# Power_ATX.net
KiCad netlist of a schematic drawn in Altium Designer
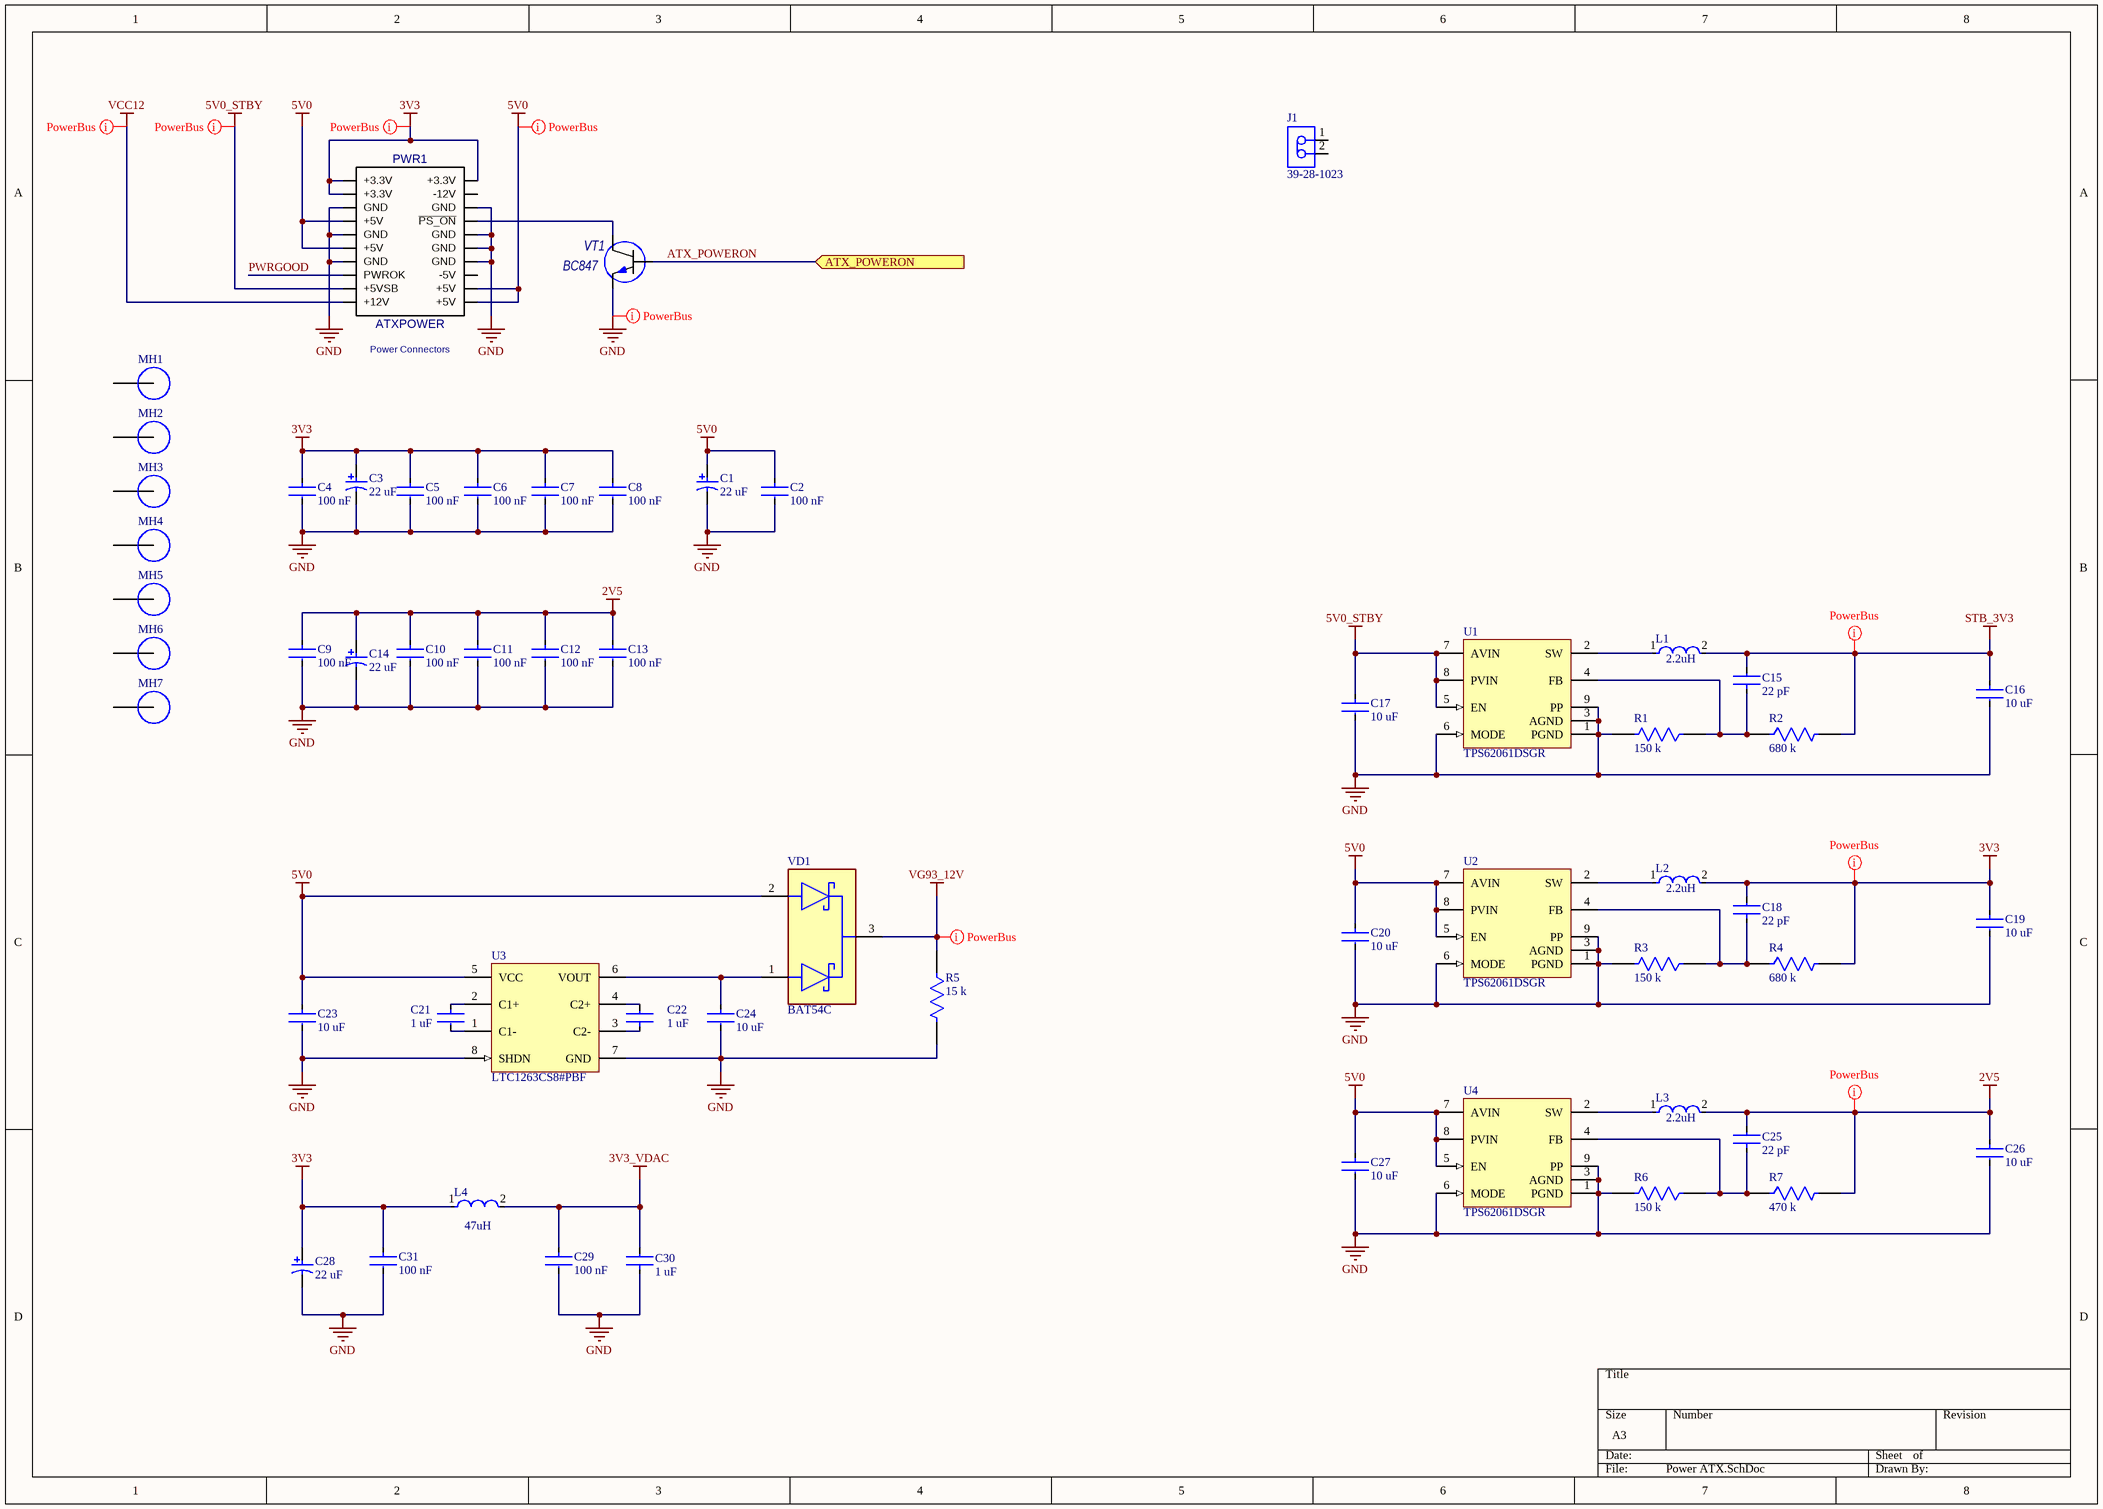
[diagram p0: Power ATX.SchDoc]

(export (version "E")
  (design (tool "Eeschema 10.0.6"))
  (components
    (comp (ref "C1")
      (value "EC1210-22uF")
      (footprint "AVX-TAJ-B-2_M")
      (description "Standard Tantalum, 22 uF, +/- 10%, 16 V, -55 to 125 degC, 2-Pin SMD (1210), RoHS, Tape and Reel")
      (fields
        (field (name "CAPACITANCE") "22 uF")
        (field (name "MANUFACTURER") "Kyocera AVX")
        (field (name "MANUFACTURER PART NUMBER") "TAJB226K016RNJ")
      )
      (libsource (lib "zxevo") (part "EC1210-22uF"))
    )
    (comp (ref "C2")
      (value "CC0805-1.5pF")
      (footprint "CC0805")
      (description "CL21 Series 0805 1.5pF 50V ±0.25pF Tolerance C0G Multilayer Ceramic Chip Capacitor")
      (fields
        (field (name "MANUFACTURER PART NUMBER") "CL21C1R5CBANNNC")
        (field (name "CAPACITANCE") "100 nF")
        (field (name "MANUFACTURER") "Samsung")
      )
      (libsource (lib "zxevo") (part "CC0805"))
    )
    (comp (ref "C3")
      (value "EC1210-22uF")
      (footprint "AVX-TAJ-B-2_M")
      (description "Standard Tantalum, 22 uF, +/- 10%, 16 V, -55 to 125 degC, 2-Pin SMD (1210), RoHS, Tape and Reel")
      (fields
        (field (name "CAPACITANCE") "22 uF")
        (field (name "MANUFACTURER") "Kyocera AVX")
        (field (name "MANUFACTURER PART NUMBER") "TAJB226K016RNJ")
      )
      (libsource (lib "zxevo") (part "EC1210-22uF"))
    )
    (comp (ref "C4")
      (value "CC0805-1.5pF")
      (footprint "CC0805")
      (description "CL21 Series 0805 1.5pF 50V ±0.25pF Tolerance C0G Multilayer Ceramic Chip Capacitor")
      (fields
        (field (name "MANUFACTURER PART NUMBER") "CL21C1R5CBANNNC")
        (field (name "CAPACITANCE") "100 nF")
        (field (name "MANUFACTURER") "Samsung")
      )
      (libsource (lib "zxevo") (part "CC0805"))
    )
    (comp (ref "C5")
      (value "CC0805-1.5pF")
      (footprint "CC0805")
      (description "CL21 Series 0805 1.5pF 50V ±0.25pF Tolerance C0G Multilayer Ceramic Chip Capacitor")
      (fields
        (field (name "MANUFACTURER PART NUMBER") "CL21C1R5CBANNNC")
        (field (name "CAPACITANCE") "100 nF")
        (field (name "MANUFACTURER") "Samsung")
      )
      (libsource (lib "zxevo") (part "CC0805"))
    )
    (comp (ref "C6")
      (value "CC0805-1.5pF")
      (footprint "CC0805")
      (description "CL21 Series 0805 1.5pF 50V ±0.25pF Tolerance C0G Multilayer Ceramic Chip Capacitor")
      (fields
        (field (name "MANUFACTURER PART NUMBER") "CL21C1R5CBANNNC")
        (field (name "CAPACITANCE") "100 nF")
        (field (name "MANUFACTURER") "Samsung")
      )
      (libsource (lib "zxevo") (part "CC0805"))
    )
    (comp (ref "C7")
      (value "CC0805-1.5pF")
      (footprint "CC0805")
      (description "CL21 Series 0805 1.5pF 50V ±0.25pF Tolerance C0G Multilayer Ceramic Chip Capacitor")
      (fields
        (field (name "MANUFACTURER PART NUMBER") "CL21C1R5CBANNNC")
        (field (name "CAPACITANCE") "100 nF")
        (field (name "MANUFACTURER") "Samsung")
      )
      (libsource (lib "zxevo") (part "CC0805"))
    )
    (comp (ref "C8")
      (value "CC0805-1.5pF")
      (footprint "CC0805")
      (description "CL21 Series 0805 1.5pF 50V ±0.25pF Tolerance C0G Multilayer Ceramic Chip Capacitor")
      (fields
        (field (name "MANUFACTURER PART NUMBER") "CL21C1R5CBANNNC")
        (field (name "CAPACITANCE") "100 nF")
        (field (name "MANUFACTURER") "Samsung")
      )
      (libsource (lib "zxevo") (part "CC0805"))
    )
    (comp (ref "C9")
      (value "CC0805-1.5pF")
      (footprint "CC0805")
      (description "CL21 Series 0805 1.5pF 50V ±0.25pF Tolerance C0G Multilayer Ceramic Chip Capacitor")
      (fields
        (field (name "MANUFACTURER PART NUMBER") "CL21C1R5CBANNNC")
        (field (name "CAPACITANCE") "100 nF")
        (field (name "MANUFACTURER") "Samsung")
      )
      (libsource (lib "zxevo") (part "CC0805"))
    )
    (comp (ref "C10")
      (value "CC0805-1.5pF")
      (footprint "CC0805")
      (description "CL21 Series 0805 1.5pF 50V ±0.25pF Tolerance C0G Multilayer Ceramic Chip Capacitor")
      (fields
        (field (name "MANUFACTURER PART NUMBER") "CL21C1R5CBANNNC")
        (field (name "CAPACITANCE") "100 nF")
        (field (name "MANUFACTURER") "Samsung")
      )
      (libsource (lib "zxevo") (part "CC0805"))
    )
    (comp (ref "C11")
      (value "CC0805-1.5pF")
      (footprint "CC0805")
      (description "CL21 Series 0805 1.5pF 50V ±0.25pF Tolerance C0G Multilayer Ceramic Chip Capacitor")
      (fields
        (field (name "MANUFACTURER PART NUMBER") "CL21C1R5CBANNNC")
        (field (name "CAPACITANCE") "100 nF")
        (field (name "MANUFACTURER") "Samsung")
      )
      (libsource (lib "zxevo") (part "CC0805"))
    )
    (comp (ref "C12")
      (value "CC0805-1.5pF")
      (footprint "CC0805")
      (description "CL21 Series 0805 1.5pF 50V ±0.25pF Tolerance C0G Multilayer Ceramic Chip Capacitor")
      (fields
        (field (name "MANUFACTURER PART NUMBER") "CL21C1R5CBANNNC")
        (field (name "CAPACITANCE") "100 nF")
        (field (name "MANUFACTURER") "Samsung")
      )
      (libsource (lib "zxevo") (part "CC0805"))
    )
    (comp (ref "C13")
      (value "CC0805-1.5pF")
      (footprint "CC0805")
      (description "CL21 Series 0805 1.5pF 50V ±0.25pF Tolerance C0G Multilayer Ceramic Chip Capacitor")
      (fields
        (field (name "MANUFACTURER PART NUMBER") "CL21C1R5CBANNNC")
        (field (name "CAPACITANCE") "100 nF")
        (field (name "MANUFACTURER") "Samsung")
      )
      (libsource (lib "zxevo") (part "CC0805"))
    )
    (comp (ref "C14")
      (value "EC1210-22uF")
      (footprint "AVX-TAJ-B-2_M")
      (description "Standard Tantalum, 22 uF, +/- 10%, 16 V, -55 to 125 degC, 2-Pin SMD (1210), RoHS, Tape and Reel")
      (fields
        (field (name "CAPACITANCE") "22 uF")
        (field (name "MANUFACTURER") "Kyocera AVX")
        (field (name "MANUFACTURER PART NUMBER") "TAJB226K016RNJ")
      )
      (libsource (lib "zxevo") (part "EC1210-22uF"))
    )
    (comp (ref "C15")
      (value "CC0805-1.5pF")
      (footprint "CC0805")
      (description "CL21 Series 0805 1.5pF 50V ±0.25pF Tolerance C0G Multilayer Ceramic Chip Capacitor")
      (fields
        (field (name "MANUFACTURER PART NUMBER") "CL21C1R5CBANNNC")
        (field (name "MANUFACTURER") "Samsung")
        (field (name "CAPACITANCE") "22 pF")
      )
      (libsource (lib "zxevo") (part "CC0805"))
    )
    (comp (ref "C16")
      (value "CC0805-1.5pF")
      (footprint "CC0805")
      (description "CL21 Series 0805 1.5pF 50V ±0.25pF Tolerance C0G Multilayer Ceramic Chip Capacitor")
      (fields
        (field (name "MANUFACTURER PART NUMBER") "CL21C1R5CBANNNC")
        (field (name "MANUFACTURER") "Samsung")
        (field (name "CAPACITANCE") "10 uF")
      )
      (libsource (lib "zxevo") (part "CC0805"))
    )
    (comp (ref "C17")
      (value "CC0805-1.5pF")
      (footprint "CC0805")
      (description "CL21 Series 0805 1.5pF 50V ±0.25pF Tolerance C0G Multilayer Ceramic Chip Capacitor")
      (fields
        (field (name "MANUFACTURER PART NUMBER") "CL21C1R5CBANNNC")
        (field (name "MANUFACTURER") "Samsung")
        (field (name "CAPACITANCE") "10 uF")
      )
      (libsource (lib "zxevo") (part "CC0805"))
    )
    (comp (ref "C18")
      (value "CC0805-1.5pF")
      (footprint "CC0805")
      (description "CL21 Series 0805 1.5pF 50V ±0.25pF Tolerance C0G Multilayer Ceramic Chip Capacitor")
      (fields
        (field (name "MANUFACTURER PART NUMBER") "CL21C1R5CBANNNC")
        (field (name "MANUFACTURER") "Samsung")
        (field (name "CAPACITANCE") "22 pF")
      )
      (libsource (lib "zxevo") (part "CC0805"))
    )
    (comp (ref "C19")
      (value "CC0805-1.5pF")
      (footprint "CC0805")
      (description "CL21 Series 0805 1.5pF 50V ±0.25pF Tolerance C0G Multilayer Ceramic Chip Capacitor")
      (fields
        (field (name "MANUFACTURER PART NUMBER") "CL21C1R5CBANNNC")
        (field (name "MANUFACTURER") "Samsung")
        (field (name "CAPACITANCE") "10 uF")
      )
      (libsource (lib "zxevo") (part "CC0805"))
    )
    (comp (ref "C20")
      (value "CC0805-1.5pF")
      (footprint "CC0805")
      (description "CL21 Series 0805 1.5pF 50V ±0.25pF Tolerance C0G Multilayer Ceramic Chip Capacitor")
      (fields
        (field (name "MANUFACTURER PART NUMBER") "CL21C1R5CBANNNC")
        (field (name "MANUFACTURER") "Samsung")
        (field (name "CAPACITANCE") "10 uF")
      )
      (libsource (lib "zxevo") (part "CC0805"))
    )
    (comp (ref "C21")
      (value "CC0805-1.5pF")
      (footprint "CC0805")
      (description "CL21 Series 0805 1.5pF 50V ±0.25pF Tolerance C0G Multilayer Ceramic Chip Capacitor")
      (fields
        (field (name "CAPACITANCE") "1 uF")
        (field (name "MANUFACTURER") "Samsung")
        (field (name "MANUFACTURER PART NUMBER") "CL21C1R5CBANNNC")
      )
      (libsource (lib "zxevo") (part "CC0805"))
    )
    (comp (ref "C22")
      (value "CC0805-1.5pF")
      (footprint "CC0805")
      (description "CL21 Series 0805 1.5pF 50V ±0.25pF Tolerance C0G Multilayer Ceramic Chip Capacitor")
      (fields
        (field (name "CAPACITANCE") "1 uF")
        (field (name "MANUFACTURER") "Samsung")
        (field (name "MANUFACTURER PART NUMBER") "CL21C1R5CBANNNC")
      )
      (libsource (lib "zxevo") (part "CC0805"))
    )
    (comp (ref "C23")
      (value "CC0805-1.5pF")
      (footprint "CC0805")
      (description "CL21 Series 0805 1.5pF 50V ±0.25pF Tolerance C0G Multilayer Ceramic Chip Capacitor")
      (fields
        (field (name "MANUFACTURER PART NUMBER") "CL21C1R5CBANNNC")
        (field (name "MANUFACTURER") "Samsung")
        (field (name "CAPACITANCE") "10 uF")
      )
      (libsource (lib "zxevo") (part "CC0805"))
    )
    (comp (ref "C24")
      (value "CC0805-1.5pF")
      (footprint "CC0805")
      (description "CL21 Series 0805 1.5pF 50V ±0.25pF Tolerance C0G Multilayer Ceramic Chip Capacitor")
      (fields
        (field (name "MANUFACTURER PART NUMBER") "CL21C1R5CBANNNC")
        (field (name "MANUFACTURER") "Samsung")
        (field (name "CAPACITANCE") "10 uF")
      )
      (libsource (lib "zxevo") (part "CC0805"))
    )
    (comp (ref "C25")
      (value "CC0805-1.5pF")
      (footprint "CC0805")
      (description "CL21 Series 0805 1.5pF 50V ±0.25pF Tolerance C0G Multilayer Ceramic Chip Capacitor")
      (fields
        (field (name "MANUFACTURER PART NUMBER") "CL21C1R5CBANNNC")
        (field (name "MANUFACTURER") "Samsung")
        (field (name "CAPACITANCE") "22 pF")
      )
      (libsource (lib "zxevo") (part "CC0805"))
    )
    (comp (ref "C26")
      (value "CC0805-1.5pF")
      (footprint "CC0805")
      (description "CL21 Series 0805 1.5pF 50V ±0.25pF Tolerance C0G Multilayer Ceramic Chip Capacitor")
      (fields
        (field (name "MANUFACTURER PART NUMBER") "CL21C1R5CBANNNC")
        (field (name "MANUFACTURER") "Samsung")
        (field (name "CAPACITANCE") "10 uF")
      )
      (libsource (lib "zxevo") (part "CC0805"))
    )
    (comp (ref "C27")
      (value "CC0805-1.5pF")
      (footprint "CC0805")
      (description "CL21 Series 0805 1.5pF 50V ±0.25pF Tolerance C0G Multilayer Ceramic Chip Capacitor")
      (fields
        (field (name "MANUFACTURER PART NUMBER") "CL21C1R5CBANNNC")
        (field (name "MANUFACTURER") "Samsung")
        (field (name "CAPACITANCE") "10 uF")
      )
      (libsource (lib "zxevo") (part "CC0805"))
    )
    (comp (ref "C28")
      (value "EC1210-22uF")
      (footprint "AVX-TAJ-B-2_M")
      (description "Standard Tantalum, 22 uF, +/- 10%, 16 V, -55 to 125 degC, 2-Pin SMD (1210), RoHS, Tape and Reel")
      (fields
        (field (name "CAPACITANCE") "22 uF")
        (field (name "MANUFACTURER") "Kyocera AVX")
        (field (name "MANUFACTURER PART NUMBER") "TAJB226K016RNJ")
      )
      (libsource (lib "zxevo") (part "EC1210-22uF"))
    )
    (comp (ref "C29")
      (value "CC0805-1.5pF")
      (footprint "CC0805")
      (description "CL21 Series 0805 1.5pF 50V ±0.25pF Tolerance C0G Multilayer Ceramic Chip Capacitor")
      (fields
        (field (name "MANUFACTURER PART NUMBER") "CL21C1R5CBANNNC")
        (field (name "CAPACITANCE") "100 nF")
        (field (name "MANUFACTURER") "Samsung")
      )
      (libsource (lib "zxevo") (part "CC0805"))
    )
    (comp (ref "C30")
      (value "CC0805-1.5pF")
      (footprint "CC0805")
      (description "CL21 Series 0805 1.5pF 50V ±0.25pF Tolerance C0G Multilayer Ceramic Chip Capacitor")
      (fields
        (field (name "CAPACITANCE") "1 uF")
        (field (name "MANUFACTURER") "Samsung")
        (field (name "MANUFACTURER PART NUMBER") "CL21C1R5CBANNNC")
      )
      (libsource (lib "zxevo") (part "CC0805"))
    )
    (comp (ref "C31")
      (value "CC0805-1.5pF")
      (footprint "CC0805")
      (description "CL21 Series 0805 1.5pF 50V ±0.25pF Tolerance C0G Multilayer Ceramic Chip Capacitor")
      (fields
        (field (name "MANUFACTURER PART NUMBER") "CL21C1R5CBANNNC")
        (field (name "CAPACITANCE") "100 nF")
        (field (name "MANUFACTURER") "Samsung")
      )
      (libsource (lib "zxevo") (part "CC0805"))
    )
    (comp (ref "J1")
      (value "39-28-1023")
      (footprint "MOLX-39-28-1023-2_V")
      (fields (field (name "MANUFACTURER") "Molex"))
      (libsource (lib "Altium Content Vault") (part "CN-2P-F-QF2"))
    )
    (comp (ref "L1")
      (value "NR6028T2R2N")
      (footprint "FP-NR6028-MFG")
      (description "SMD Power Inductors 2.2uH ±30% 3.7A 26mΩ")
      (fields (field (name "TOLERANCE") "30%") (field (name "INDUCTANCE") "2.2uH"))
      (libsource (lib "Altium Content Vault") (part "725321dda6339637d4d059423bc1c3c"))
    )
    (comp (ref "L2")
      (value "NR6028T2R2N")
      (footprint "FP-NR6028-MFG")
      (description "SMD Power Inductors 2.2uH ±30% 3.7A 26mΩ")
      (fields (field (name "TOLERANCE") "30%") (field (name "INDUCTANCE") "2.2uH"))
      (libsource (lib "Altium Content Vault") (part "725321dda6339637d4d059423bc1c3c"))
    )
    (comp (ref "L3")
      (value "NR6028T2R2N")
      (footprint "FP-NR6028-MFG")
      (description "SMD Power Inductors 2.2uH ±30% 3.7A 26mΩ")
      (fields (field (name "TOLERANCE") "30%") (field (name "INDUCTANCE") "2.2uH"))
      (libsource (lib "Altium Content Vault") (part "725321dda6339637d4d059423bc1c3c"))
    )
    (comp (ref "L4")
      (value "NR6028T470M")
      (footprint "FP-NR6028-MFG")
      (description "SMD Power Inductors 47uH ±20% 0.92A 0.39Ω")
      (fields (field (name "INDUCTANCE") "47uH") (field (name "TOLERANCE") "20%"))
      (libsource (lib "Altium Content Vault") (part "725321dda6339637d4d059423bc1c3c"))
    )
    (comp (ref "MH1")
      (value "MOUNT HOLE")
      (footprint "MOUNT HOLE")
      (libsource (lib "zxevo") (part "MOUNT HOLE"))
    )
    (comp (ref "MH2")
      (value "MOUNT HOLE")
      (footprint "MOUNT HOLE")
      (libsource (lib "zxevo") (part "MOUNT HOLE"))
    )
    (comp (ref "MH3")
      (value "MOUNT HOLE")
      (footprint "MOUNT HOLE")
      (libsource (lib "zxevo") (part "MOUNT HOLE"))
    )
    (comp (ref "MH4")
      (value "MOUNT HOLE")
      (footprint "MOUNT HOLE")
      (libsource (lib "zxevo") (part "MOUNT HOLE"))
    )
    (comp (ref "MH5")
      (value "MOUNT HOLE")
      (footprint "MOUNT HOLE")
      (libsource (lib "zxevo") (part "MOUNT HOLE"))
    )
    (comp (ref "MH6")
      (value "MOUNT HOLE")
      (footprint "MOUNT HOLE")
      (libsource (lib "zxevo") (part "MOUNT HOLE"))
    )
    (comp (ref "MH7")
      (value "MOUNT HOLE")
      (footprint "MOUNT HOLE")
      (libsource (lib "zxevo") (part "MOUNT HOLE"))
    )
    (comp (ref "PWR1") (value "ATXPOWER") (footprint "ATXPOWER") (libsource (lib "zxevo") (part "ATXPOWER")))
    (comp (ref "R1")
      (value "CR0805-51")
      (footprint "CR0805")
      (description "51Ω ±0.5% 0.1W 1/10W Chip Resistor 0805 (2012 Metric) Thin Film")
      (fields
        (field (name "MANUFACTURER PART NUMBER") "RR1220Q-510-D")
        (field (name "MANUFACTURER") "Susumu")
        (field (name "RESISTANCE") "150 k")
      )
      (libsource (lib "zxevo") (part "CR0805"))
    )
    (comp (ref "R2")
      (value "CR0805-51")
      (footprint "CR0805")
      (description "51Ω ±0.5% 0.1W 1/10W Chip Resistor 0805 (2012 Metric) Thin Film")
      (fields
        (field (name "MANUFACTURER PART NUMBER") "RR1220Q-510-D")
        (field (name "MANUFACTURER") "Susumu")
        (field (name "RESISTANCE") "680 k")
      )
      (libsource (lib "zxevo") (part "CR0805"))
    )
    (comp (ref "R3")
      (value "CR0805-51")
      (footprint "CR0805")
      (description "51Ω ±0.5% 0.1W 1/10W Chip Resistor 0805 (2012 Metric) Thin Film")
      (fields
        (field (name "MANUFACTURER PART NUMBER") "RR1220Q-510-D")
        (field (name "MANUFACTURER") "Susumu")
        (field (name "RESISTANCE") "150 k")
      )
      (libsource (lib "zxevo") (part "CR0805"))
    )
    (comp (ref "R4")
      (value "CR0805-51")
      (footprint "CR0805")
      (description "51Ω ±0.5% 0.1W 1/10W Chip Resistor 0805 (2012 Metric) Thin Film")
      (fields
        (field (name "MANUFACTURER PART NUMBER") "RR1220Q-510-D")
        (field (name "MANUFACTURER") "Susumu")
        (field (name "RESISTANCE") "680 k")
      )
      (libsource (lib "zxevo") (part "CR0805"))
    )
    (comp (ref "R5")
      (value "CR0805-51")
      (footprint "CR0805")
      (description "51Ω ±0.5% 0.1W 1/10W Chip Resistor 0805 (2012 Metric) Thin Film")
      (fields
        (field (name "MANUFACTURER PART NUMBER") "RR1220Q-510-D")
        (field (name "MANUFACTURER") "Susumu")
        (field (name "RESISTANCE") "15 k")
      )
      (libsource (lib "zxevo") (part "CR0805"))
    )
    (comp (ref "R6")
      (value "CR0805-51")
      (footprint "CR0805")
      (description "51Ω ±0.5% 0.1W 1/10W Chip Resistor 0805 (2012 Metric) Thin Film")
      (fields
        (field (name "MANUFACTURER PART NUMBER") "RR1220Q-510-D")
        (field (name "MANUFACTURER") "Susumu")
        (field (name "RESISTANCE") "150 k")
      )
      (libsource (lib "zxevo") (part "CR0805"))
    )
    (comp (ref "R7")
      (value "CR0805-51")
      (footprint "CR0805")
      (description "51Ω ±0.5% 0.1W 1/10W Chip Resistor 0805 (2012 Metric) Thin Film")
      (fields
        (field (name "MANUFACTURER PART NUMBER") "RR1220Q-510-D")
        (field (name "MANUFACTURER") "Susumu")
        (field (name "RESISTANCE") "470 k")
      )
      (libsource (lib "zxevo") (part "CR0805"))
    )
    (comp (ref "U1")
      (value "TPS62061DSGR")
      (footprint "DSG0008A_V")
      (fields (field (name "MANUFACTURER") "Texas Instruments"))
      (libsource (lib "Altium Content Vault") (part "TI-TPS62061DSG8-1600X900TP"))
    )
    (comp (ref "U2")
      (value "TPS62061DSGR")
      (footprint "DSG0008A_V")
      (fields (field (name "MANUFACTURER") "Texas Instruments"))
      (libsource (lib "Altium Content Vault") (part "TI-TPS62061DSG8-1600X900TP"))
    )
    (comp (ref "U3")
      (value "LTC1263CS8#PBF")
      (footprint "LT-S8-8_N")
      (fields (field (name "MANUFACTURER") "Linear Technology"))
      (libsource (lib "Altium Content Vault") (part "LT-LTC1262_1263-8"))
    )
    (comp (ref "U4")
      (value "TPS62061DSGR")
      (footprint "DSG0008A_V")
      (fields (field (name "MANUFACTURER") "Texas Instruments"))
      (libsource (lib "Altium Content Vault") (part "TI-TPS62061DSG8-1600X900TP"))
    )
    (comp (ref "VD1")
      (value "BAT54C")
      (footprint "SOT-23")
      (description "DIODE ARRAY SCHOTTKY 30V SOT23-3")
      (fields (field (name "MANUFACTURER") "ON Semiconductor / Fairchild"))
      (libsource (lib "zxevo") (part "BAT54C"))
    )
    (comp (ref "VT1") (value "BC847") (footprint "SOT-23") (libsource (lib "zxevo") (part "BC847")))
  )
  (nets
    (net (code "1") (name "/ATX_POWERON") (class "Default")
      (node (ref "VT1") (pin "1") (pinfunction "base_1") (pintype "passive"))
    )
    (net (code "2") (name "/PWRGOOD") (class "Default")
      (node (ref "PWR1") (pin "8") (pinfunction "PWROK_8") (pintype "passive"))
    )
    (net (code "3") (name "2V5") (class "Default")
      (node (ref "C10") (pin "1") (pinfunction "1_1") (pintype "passive"))
      (node (ref "C11") (pin "1") (pinfunction "1_1") (pintype "passive"))
      (node (ref "C12") (pin "1") (pinfunction "1_1") (pintype "passive"))
      (node (ref "C13") (pin "1") (pinfunction "1_1") (pintype "passive"))
      (node (ref "C14") (pin "1") (pinfunction "1_1") (pintype "passive"))
      (node (ref "C25") (pin "2") (pinfunction "2_2") (pintype "passive"))
      (node (ref "C26") (pin "1") (pinfunction "1_1") (pintype "passive"))
      (node (ref "C9") (pin "1") (pinfunction "1_1") (pintype "passive"))
      (node (ref "L3") (pin "2") (pinfunction "2_2") (pintype "passive"))
      (node (ref "R7") (pin "2") (pinfunction "2_2") (pintype "passive"))
    )
    (net (code "4") (name "3V3") (class "Default")
      (node (ref "C18") (pin "2") (pinfunction "2_2") (pintype "passive"))
      (node (ref "C19") (pin "1") (pinfunction "1_1") (pintype "passive"))
      (node (ref "C28") (pin "1") (pinfunction "1_1") (pintype "passive"))
      (node (ref "C3") (pin "1") (pinfunction "1_1") (pintype "passive"))
      (node (ref "C31") (pin "1") (pinfunction "1_1") (pintype "passive"))
      (node (ref "C4") (pin "1") (pinfunction "1_1") (pintype "passive"))
      (node (ref "C5") (pin "1") (pinfunction "1_1") (pintype "passive"))
      (node (ref "C6") (pin "1") (pinfunction "1_1") (pintype "passive"))
      (node (ref "C7") (pin "1") (pinfunction "1_1") (pintype "passive"))
      (node (ref "C8") (pin "1") (pinfunction "1_1") (pintype "passive"))
      (node (ref "L2") (pin "2") (pinfunction "2_2") (pintype "passive"))
      (node (ref "L4") (pin "1") (pinfunction "1_1") (pintype "passive"))
      (node (ref "PWR1") (pin "1") (pinfunction "+3.3V_1") (pintype "passive"))
      (node (ref "PWR1") (pin "11") (pinfunction "+3.3V_11") (pintype "passive"))
      (node (ref "PWR1") (pin "2") (pinfunction "+3.3V_2") (pintype "passive"))
      (node (ref "R4") (pin "2") (pinfunction "2_2") (pintype "passive"))
    )
    (net (code "5") (name "3V3_VDAC") (class "Default")
      (node (ref "C29") (pin "1") (pinfunction "1_1") (pintype "passive"))
      (node (ref "C30") (pin "2") (pinfunction "2_2") (pintype "passive"))
      (node (ref "L4") (pin "2") (pinfunction "2_2") (pintype "passive"))
    )
    (net (code "6") (name "5V0") (class "Default")
      (node (ref "C1") (pin "1") (pinfunction "1_1") (pintype "passive"))
      (node (ref "C2") (pin "1") (pinfunction "1_1") (pintype "passive"))
      (node (ref "C20") (pin "1") (pinfunction "1_1") (pintype "passive"))
      (node (ref "C23") (pin "1") (pinfunction "1_1") (pintype "passive"))
      (node (ref "C27") (pin "1") (pinfunction "1_1") (pintype "passive"))
      (node (ref "PWR1") (pin "19") (pinfunction "+5V_19") (pintype "passive"))
      (node (ref "PWR1") (pin "20") (pinfunction "+5V_20") (pintype "passive"))
      (node (ref "PWR1") (pin "4") (pinfunction "+5V_4") (pintype "passive"))
      (node (ref "PWR1") (pin "6") (pinfunction "+5V_6") (pintype "passive"))
      (node (ref "U2") (pin "5") (pinfunction "EN_5") (pintype "input"))
      (node (ref "U2") (pin "7") (pinfunction "AVIN_7") (pintype "power_in"))
      (node (ref "U2") (pin "8") (pinfunction "PVIN_8") (pintype "power_in"))
      (node (ref "U3") (pin "5") (pinfunction "VCC_5") (pintype "power_in"))
      (node (ref "U4") (pin "5") (pinfunction "EN_5") (pintype "input"))
      (node (ref "U4") (pin "7") (pinfunction "AVIN_7") (pintype "power_in"))
      (node (ref "U4") (pin "8") (pinfunction "PVIN_8") (pintype "power_in"))
      (node (ref "VD1") (pin "2") (pinfunction "2_ANODE_2") (pintype "passive"))
    )
    (net (code "7") (name "5V0_STBY") (class "Default")
      (node (ref "C17") (pin "1") (pinfunction "1_1") (pintype "passive"))
      (node (ref "PWR1") (pin "9") (pinfunction "+5VSB_9") (pintype "passive"))
      (node (ref "U1") (pin "5") (pinfunction "EN_5") (pintype "input"))
      (node (ref "U1") (pin "7") (pinfunction "AVIN_7") (pintype "power_in"))
      (node (ref "U1") (pin "8") (pinfunction "PVIN_8") (pintype "power_in"))
    )
    (net (code "8") (name "GND") (class "Default")
      (node (ref "C1") (pin "2") (pinfunction "2_2") (pintype "passive"))
      (node (ref "C10") (pin "2") (pinfunction "2_2") (pintype "passive"))
      (node (ref "C11") (pin "2") (pinfunction "2_2") (pintype "passive"))
      (node (ref "C12") (pin "2") (pinfunction "2_2") (pintype "passive"))
      (node (ref "C13") (pin "2") (pinfunction "2_2") (pintype "passive"))
      (node (ref "C14") (pin "2") (pinfunction "2_2") (pintype "passive"))
      (node (ref "C16") (pin "2") (pinfunction "2_2") (pintype "passive"))
      (node (ref "C17") (pin "2") (pinfunction "2_2") (pintype "passive"))
      (node (ref "C19") (pin "2") (pinfunction "2_2") (pintype "passive"))
      (node (ref "C2") (pin "2") (pinfunction "2_2") (pintype "passive"))
      (node (ref "C20") (pin "2") (pinfunction "2_2") (pintype "passive"))
      (node (ref "C23") (pin "2") (pinfunction "2_2") (pintype "passive"))
      (node (ref "C24") (pin "2") (pinfunction "2_2") (pintype "passive"))
      (node (ref "C26") (pin "2") (pinfunction "2_2") (pintype "passive"))
      (node (ref "C27") (pin "2") (pinfunction "2_2") (pintype "passive"))
      (node (ref "C28") (pin "2") (pinfunction "2_2") (pintype "passive"))
      (node (ref "C29") (pin "2") (pinfunction "2_2") (pintype "passive"))
      (node (ref "C3") (pin "2") (pinfunction "2_2") (pintype "passive"))
      (node (ref "C30") (pin "1") (pinfunction "1_1") (pintype "passive"))
      (node (ref "C31") (pin "2") (pinfunction "2_2") (pintype "passive"))
      (node (ref "C4") (pin "2") (pinfunction "2_2") (pintype "passive"))
      (node (ref "C5") (pin "2") (pinfunction "2_2") (pintype "passive"))
      (node (ref "C6") (pin "2") (pinfunction "2_2") (pintype "passive"))
      (node (ref "C7") (pin "2") (pinfunction "2_2") (pintype "passive"))
      (node (ref "C8") (pin "2") (pinfunction "2_2") (pintype "passive"))
      (node (ref "C9") (pin "2") (pinfunction "2_2") (pintype "passive"))
      (node (ref "PWR1") (pin "13") (pinfunction "GND_13") (pintype "passive"))
      (node (ref "PWR1") (pin "15") (pinfunction "GND_15") (pintype "passive"))
      (node (ref "PWR1") (pin "16") (pinfunction "GND_16") (pintype "passive"))
      (node (ref "PWR1") (pin "17") (pinfunction "GND_17") (pintype "passive"))
      (node (ref "PWR1") (pin "3") (pinfunction "GND_3") (pintype "passive"))
      (node (ref "PWR1") (pin "5") (pinfunction "GND_5") (pintype "passive"))
      (node (ref "PWR1") (pin "7") (pinfunction "GND_7") (pintype "passive"))
      (node (ref "R1") (pin "2") (pinfunction "2_2") (pintype "passive"))
      (node (ref "R3") (pin "2") (pinfunction "2_2") (pintype "passive"))
      (node (ref "R5") (pin "2") (pinfunction "2_2") (pintype "passive"))
      (node (ref "R6") (pin "2") (pinfunction "2_2") (pintype "passive"))
      (node (ref "U1") (pin "1") (pinfunction "PGND_1") (pintype "power_in"))
      (node (ref "U1") (pin "3") (pinfunction "AGND_3") (pintype "power_in"))
      (node (ref "U1") (pin "6") (pinfunction "MODE_6") (pintype "input"))
      (node (ref "U1") (pin "9") (pinfunction "PP_9") (pintype "power_in"))
      (node (ref "U2") (pin "1") (pinfunction "PGND_1") (pintype "power_in"))
      (node (ref "U2") (pin "3") (pinfunction "AGND_3") (pintype "power_in"))
      (node (ref "U2") (pin "6") (pinfunction "MODE_6") (pintype "input"))
      (node (ref "U2") (pin "9") (pinfunction "PP_9") (pintype "power_in"))
      (node (ref "U3") (pin "7") (pinfunction "GND_7") (pintype "power_in"))
      (node (ref "U3") (pin "8") (pinfunction "SHDN_8") (pintype "input"))
      (node (ref "U4") (pin "1") (pinfunction "PGND_1") (pintype "power_in"))
      (node (ref "U4") (pin "3") (pinfunction "AGND_3") (pintype "power_in"))
      (node (ref "U4") (pin "6") (pinfunction "MODE_6") (pintype "input"))
      (node (ref "U4") (pin "9") (pinfunction "PP_9") (pintype "power_in"))
      (node (ref "VT1") (pin "2") (pinfunction "emitter_2") (pintype "passive"))
    )
    (net (code "9") (name "Net-(PWR1-~{PS_ON})") (class "Default")
      (node (ref "PWR1") (pin "14") (pinfunction "~{PS_ON}_14") (pintype "passive"))
      (node (ref "VT1") (pin "3") (pinfunction "collector_3") (pintype "passive"))
    )
    (net (code "10") (name "Net-(U1-FB)") (class "Default")
      (node (ref "C15") (pin "1") (pinfunction "1_1") (pintype "passive"))
      (node (ref "R1") (pin "1") (pinfunction "1_1") (pintype "passive"))
      (node (ref "R2") (pin "1") (pinfunction "1_1") (pintype "passive"))
      (node (ref "U1") (pin "4") (pinfunction "FB_4") (pintype "passive"))
    )
    (net (code "11") (name "Net-(U1-SW)") (class "Default")
      (node (ref "L1") (pin "1") (pinfunction "1_1") (pintype "passive"))
      (node (ref "U1") (pin "2") (pinfunction "SW_2") (pintype "power_in"))
    )
    (net (code "12") (name "Net-(U2-FB)") (class "Default")
      (node (ref "C18") (pin "1") (pinfunction "1_1") (pintype "passive"))
      (node (ref "R3") (pin "1") (pinfunction "1_1") (pintype "passive"))
      (node (ref "R4") (pin "1") (pinfunction "1_1") (pintype "passive"))
      (node (ref "U2") (pin "4") (pinfunction "FB_4") (pintype "passive"))
    )
    (net (code "13") (name "Net-(U2-SW)") (class "Default")
      (node (ref "L2") (pin "1") (pinfunction "1_1") (pintype "passive"))
      (node (ref "U2") (pin "2") (pinfunction "SW_2") (pintype "power_in"))
    )
    (net (code "14") (name "Net-(U3-C1+)") (class "Default")
      (node (ref "C21") (pin "1") (pinfunction "1_1") (pintype "passive"))
      (node (ref "U3") (pin "2") (pinfunction "C1+_2") (pintype "passive"))
    )
    (net (code "15") (name "Net-(U3-C1-)") (class "Default")
      (node (ref "C21") (pin "2") (pinfunction "2_2") (pintype "passive"))
      (node (ref "U3") (pin "1") (pinfunction "C1-_1") (pintype "passive"))
    )
    (net (code "16") (name "Net-(U3-C2+)") (class "Default")
      (node (ref "C22") (pin "2") (pinfunction "2_2") (pintype "passive"))
      (node (ref "U3") (pin "4") (pinfunction "C2+_4") (pintype "passive"))
    )
    (net (code "17") (name "Net-(U3-C2-)") (class "Default")
      (node (ref "C22") (pin "1") (pinfunction "1_1") (pintype "passive"))
      (node (ref "U3") (pin "3") (pinfunction "C2-_3") (pintype "passive"))
    )
    (net (code "18") (name "Net-(U3-VOUT)") (class "Default")
      (node (ref "C24") (pin "1") (pinfunction "1_1") (pintype "passive"))
      (node (ref "U3") (pin "6") (pinfunction "VOUT_6") (pintype "power_in"))
      (node (ref "VD1") (pin "1") (pinfunction "1_ANODE_1") (pintype "passive"))
    )
    (net (code "19") (name "Net-(U4-FB)") (class "Default")
      (node (ref "C25") (pin "1") (pinfunction "1_1") (pintype "passive"))
      (node (ref "R6") (pin "1") (pinfunction "1_1") (pintype "passive"))
      (node (ref "R7") (pin "1") (pinfunction "1_1") (pintype "passive"))
      (node (ref "U4") (pin "4") (pinfunction "FB_4") (pintype "passive"))
    )
    (net (code "20") (name "Net-(U4-SW)") (class "Default")
      (node (ref "L3") (pin "1") (pinfunction "1_1") (pintype "passive"))
      (node (ref "U4") (pin "2") (pinfunction "SW_2") (pintype "power_in"))
    )
    (net (code "21") (name "STB_3V3") (class "Default")
      (node (ref "C15") (pin "2") (pinfunction "2_2") (pintype "passive"))
      (node (ref "C16") (pin "1") (pinfunction "1_1") (pintype "passive"))
      (node (ref "L1") (pin "2") (pinfunction "2_2") (pintype "passive"))
      (node (ref "R2") (pin "2") (pinfunction "2_2") (pintype "passive"))
    )
    (net (code "22") (name "VCC12") (class "Default")
      (node (ref "PWR1") (pin "10") (pinfunction "+12V_10") (pintype "passive"))
    )
    (net (code "23") (name "VG93_12V") (class "Default")
      (node (ref "R5") (pin "1") (pinfunction "1_1") (pintype "passive"))
      (node (ref "VD1") (pin "3") (pinfunction "COMMON_CATHODE_3") (pintype "passive"))
    )
    (net (code "24") (name "unconnected-(J1-Pad1)") (class "Default")
      (node (ref "J1") (pin "1") (pinfunction "1_1") (pintype "passive"))
    )
    (net (code "25") (name "unconnected-(J1-Pad2)") (class "Default")
      (node (ref "J1") (pin "2") (pinfunction "2_2") (pintype "passive"))
    )
    (net (code "26") (name "unconnected-(MH1-55-Pad0)") (class "Default")
      (node (ref "MH1") (pin "0") (pinfunction "55_0") (pintype "passive"))
    )
    (net (code "27") (name "unconnected-(MH2-55-Pad0)") (class "Default")
      (node (ref "MH2") (pin "0") (pinfunction "55_0") (pintype "passive"))
    )
    (net (code "28") (name "unconnected-(MH3-55-Pad0)") (class "Default")
      (node (ref "MH3") (pin "0") (pinfunction "55_0") (pintype "passive"))
    )
    (net (code "29") (name "unconnected-(MH4-55-Pad0)") (class "Default")
      (node (ref "MH4") (pin "0") (pinfunction "55_0") (pintype "passive"))
    )
    (net (code "30") (name "unconnected-(MH5-55-Pad0)") (class "Default")
      (node (ref "MH5") (pin "0") (pinfunction "55_0") (pintype "passive"))
    )
    (net (code "31") (name "unconnected-(MH6-55-Pad0)") (class "Default")
      (node (ref "MH6") (pin "0") (pinfunction "55_0") (pintype "passive"))
    )
    (net (code "32") (name "unconnected-(MH7-55-Pad0)") (class "Default")
      (node (ref "MH7") (pin "0") (pinfunction "55_0") (pintype "passive"))
    )
    (net (code "33") (name "unconnected-(PWR1--5V-Pad18)") (class "Default")
      (node (ref "PWR1") (pin "18") (pinfunction "-5V_18") (pintype "passive"))
    )
    (net (code "34") (name "unconnected-(PWR1--12V-Pad12)") (class "Default")
      (node (ref "PWR1") (pin "12") (pinfunction "-12V_12") (pintype "passive"))
    )
  )
)
